# schematic_v1.net
KiCad netlist of a schematic drawn in EasyEDA
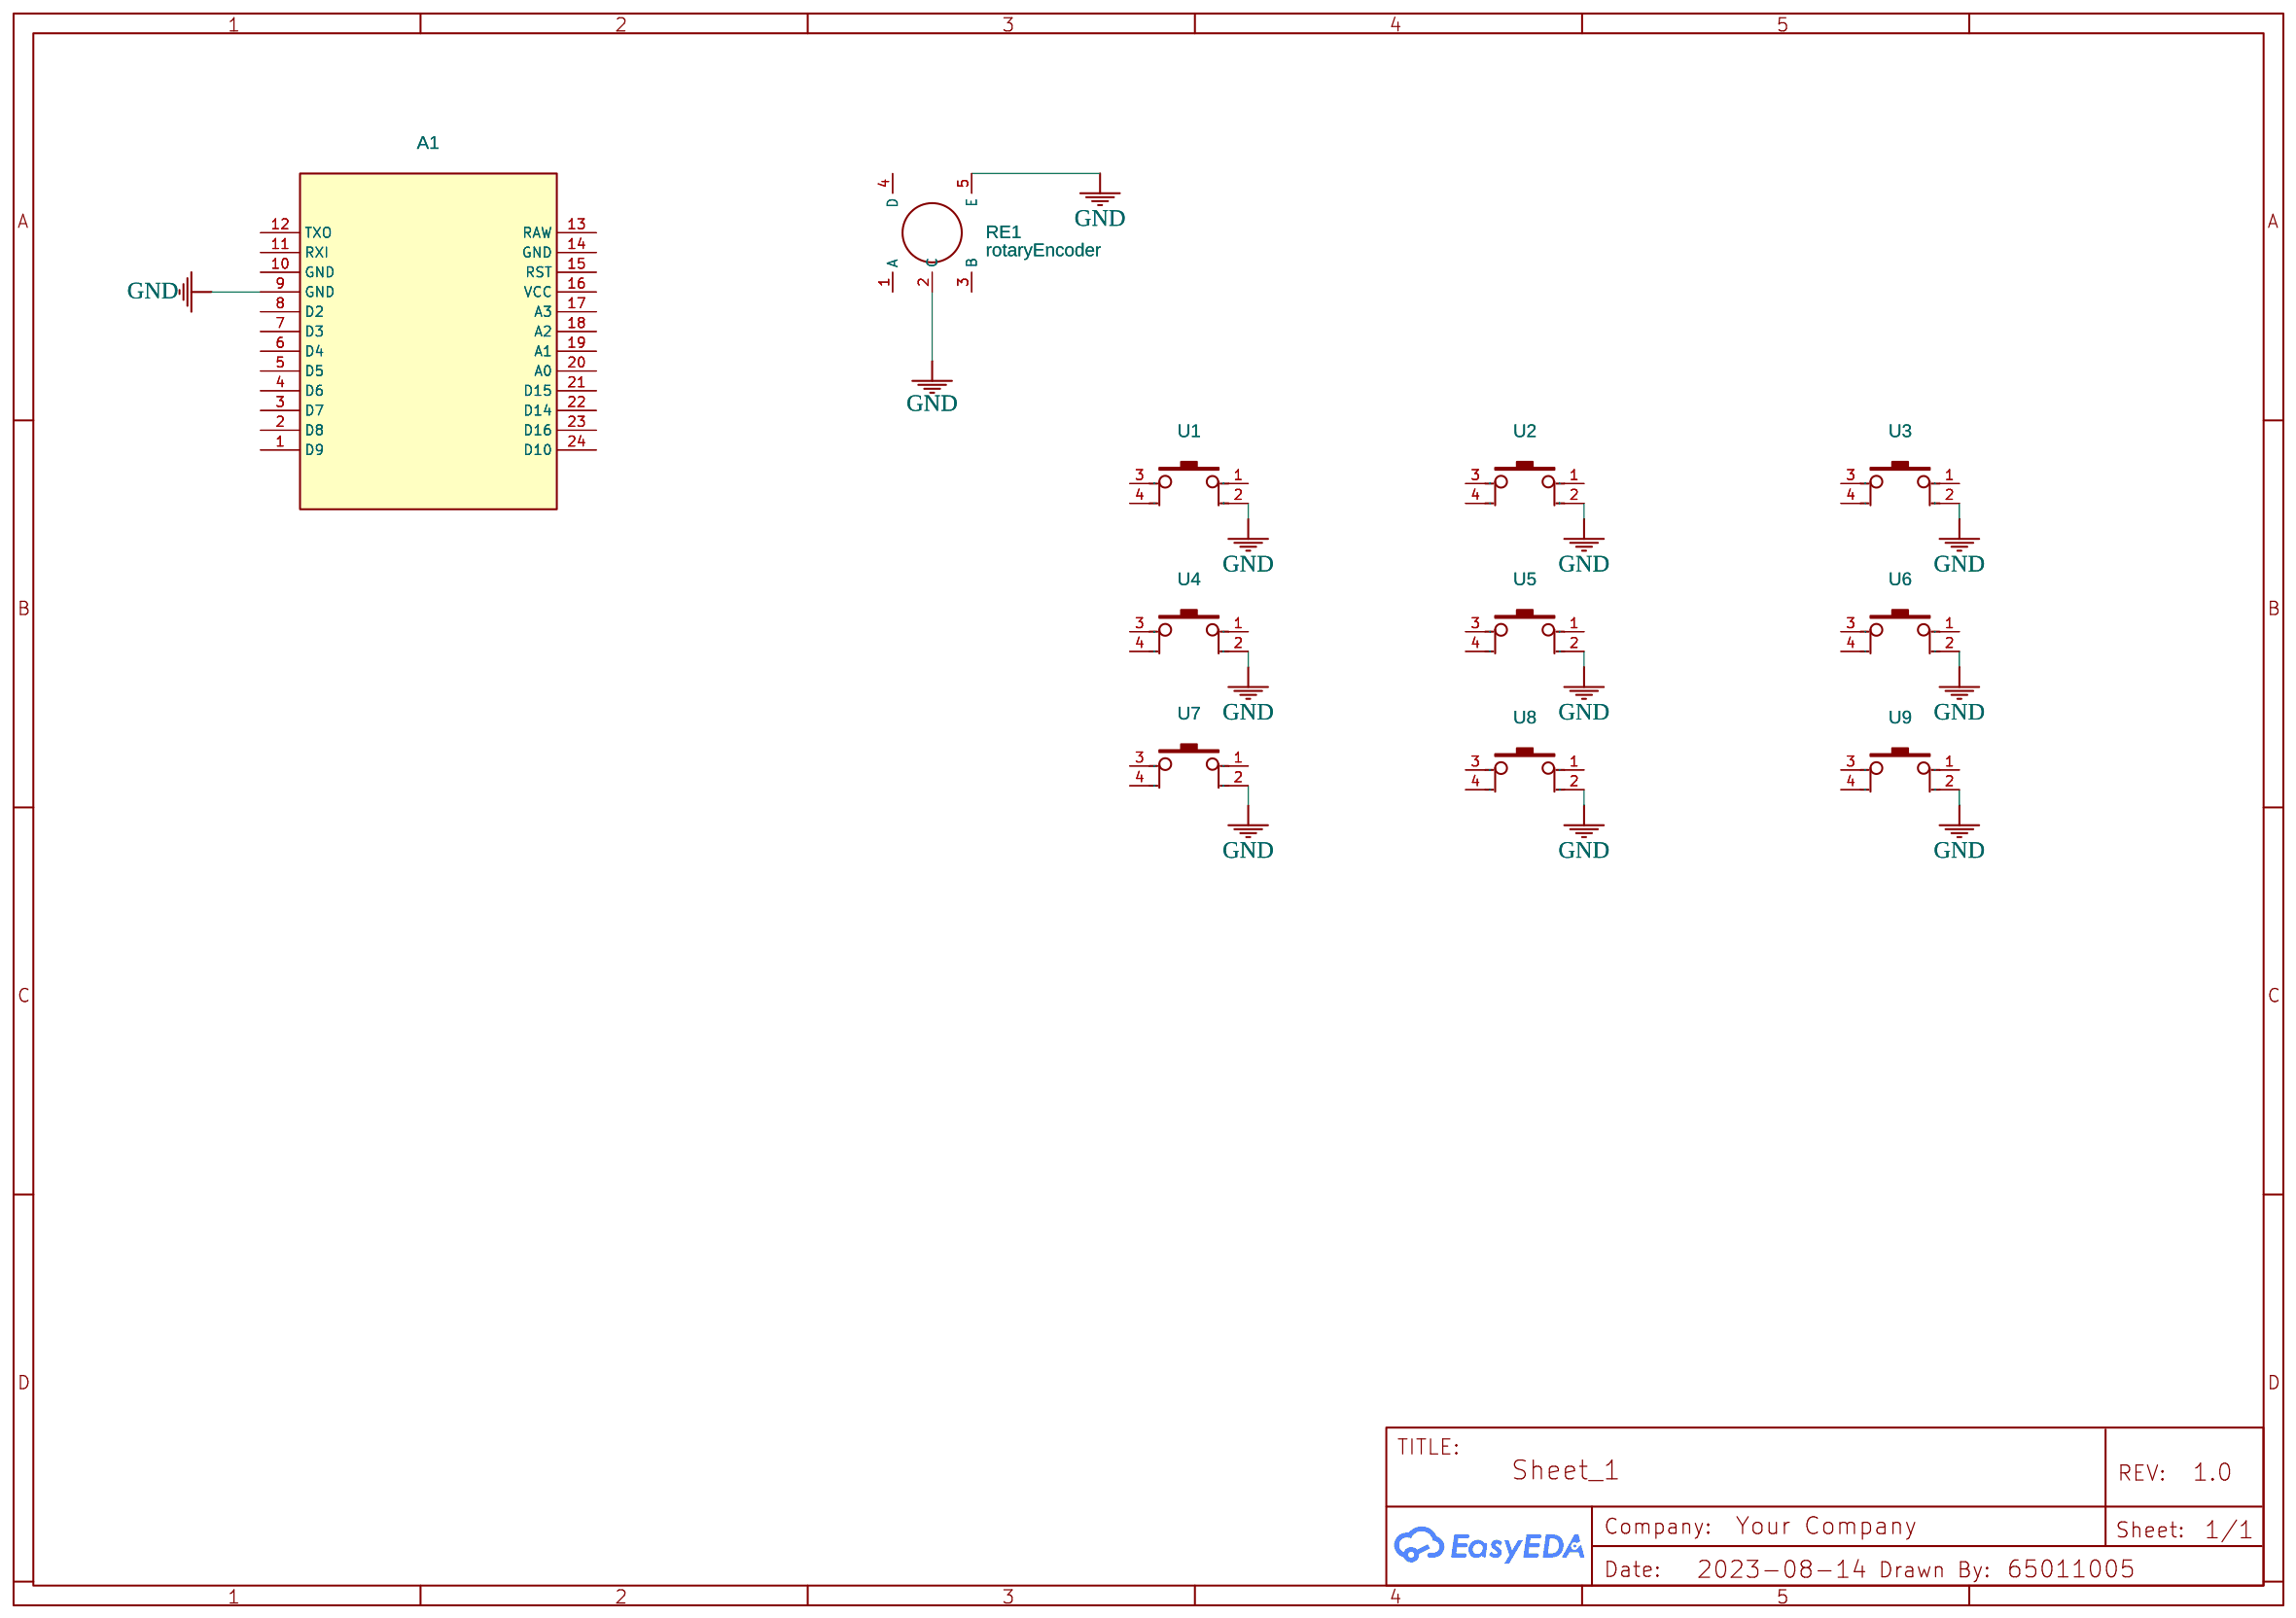
[diagram p0: schematic sheet]

(export (version "E")
  (design (tool "Eeschema 10.0.6"))
  (components
    (comp (ref "A1") (value "NO") (libsource (lib "") (part "Pro Micro - 5V")))
    (comp (ref "RE1") (value "rotaryEncoder") (libsource (lib "") (part "rotaryEncoder")))
    (comp (ref "U1") (value "NO") (libsource (lib "") (part "10mm pushbutton switch")))
    (comp (ref "U2") (value "NO") (libsource (lib "") (part "10mm pushbutton switch")))
    (comp (ref "U3") (value "NO") (libsource (lib "") (part "10mm pushbutton switch")))
    (comp (ref "U4") (value "NO") (libsource (lib "") (part "10mm pushbutton switch")))
    (comp (ref "U5") (value "NO") (libsource (lib "") (part "10mm pushbutton switch")))
    (comp (ref "U6") (value "NO") (libsource (lib "") (part "10mm pushbutton switch")))
    (comp (ref "U7") (value "NO") (libsource (lib "") (part "10mm pushbutton switch")))
    (comp (ref "U8") (value "NO") (libsource (lib "") (part "10mm pushbutton switch")))
    (comp (ref "U9") (value "NO") (libsource (lib "") (part "10mm pushbutton switch")))
  )
  (nets
    (net (code "1") (name "GND") (class "Default")
      (node (ref "A1") (pin "9") (pinfunction "GND_9") (pintype "unspecified"))
      (node (ref "RE1") (pin "2") (pinfunction "C_2") (pintype "unspecified"))
      (node (ref "RE1") (pin "5") (pinfunction "E_5") (pintype "unspecified"))
      (node (ref "U1") (pin "2") (pinfunction "2_2") (pintype "input"))
      (node (ref "U2") (pin "2") (pinfunction "2_2") (pintype "input"))
      (node (ref "U3") (pin "2") (pinfunction "2_2") (pintype "input"))
      (node (ref "U4") (pin "2") (pinfunction "2_2") (pintype "input"))
      (node (ref "U5") (pin "2") (pinfunction "2_2") (pintype "input"))
      (node (ref "U6") (pin "2") (pinfunction "2_2") (pintype "input"))
      (node (ref "U7") (pin "2") (pinfunction "2_2") (pintype "input"))
      (node (ref "U8") (pin "2") (pinfunction "2_2") (pintype "input"))
      (node (ref "U9") (pin "2") (pinfunction "2_2") (pintype "input"))
    )
    (net (code "2") (name "unconnected-(A1-A0-Pad20)") (class "Default")
      (node (ref "A1") (pin "20") (pinfunction "A0_20") (pintype "unspecified"))
    )
    (net (code "3") (name "unconnected-(A1-A1-Pad19)") (class "Default")
      (node (ref "A1") (pin "19") (pinfunction "A1_19") (pintype "unspecified"))
    )
    (net (code "4") (name "unconnected-(A1-A2-Pad18)") (class "Default")
      (node (ref "A1") (pin "18") (pinfunction "A2_18") (pintype "unspecified"))
    )
    (net (code "5") (name "unconnected-(A1-A3-Pad17)") (class "Default")
      (node (ref "A1") (pin "17") (pinfunction "A3_17") (pintype "unspecified"))
    )
    (net (code "6") (name "unconnected-(A1-D2-Pad8)") (class "Default")
      (node (ref "A1") (pin "8") (pinfunction "D2_8") (pintype "unspecified"))
    )
    (net (code "7") (name "unconnected-(A1-D3-Pad7)") (class "Default")
      (node (ref "A1") (pin "7") (pinfunction "D3_7") (pintype "unspecified"))
    )
    (net (code "8") (name "unconnected-(A1-D4-Pad6)") (class "Default")
      (node (ref "A1") (pin "6") (pinfunction "D4_6") (pintype "unspecified"))
    )
    (net (code "9") (name "unconnected-(A1-D5-Pad5)") (class "Default")
      (node (ref "A1") (pin "5") (pinfunction "D5_5") (pintype "unspecified"))
    )
    (net (code "10") (name "unconnected-(A1-D6-Pad4)") (class "Default")
      (node (ref "A1") (pin "4") (pinfunction "D6_4") (pintype "unspecified"))
    )
    (net (code "11") (name "unconnected-(A1-D7-Pad3)") (class "Default")
      (node (ref "A1") (pin "3") (pinfunction "D7_3") (pintype "unspecified"))
    )
    (net (code "12") (name "unconnected-(A1-D8-Pad2)") (class "Default")
      (node (ref "A1") (pin "2") (pinfunction "D8_2") (pintype "unspecified"))
    )
    (net (code "13") (name "unconnected-(A1-D9-Pad1)") (class "Default")
      (node (ref "A1") (pin "1") (pinfunction "D9_1") (pintype "unspecified"))
    )
    (net (code "14") (name "unconnected-(A1-D10-Pad24)") (class "Default")
      (node (ref "A1") (pin "24") (pinfunction "D10_24") (pintype "unspecified"))
    )
    (net (code "15") (name "unconnected-(A1-D14-Pad22)") (class "Default")
      (node (ref "A1") (pin "22") (pinfunction "D14_22") (pintype "unspecified"))
    )
    (net (code "16") (name "unconnected-(A1-D15-Pad21)") (class "Default")
      (node (ref "A1") (pin "21") (pinfunction "D15_21") (pintype "unspecified"))
    )
    (net (code "17") (name "unconnected-(A1-D16-Pad23)") (class "Default")
      (node (ref "A1") (pin "23") (pinfunction "D16_23") (pintype "unspecified"))
    )
    (net (code "18") (name "unconnected-(A1-GND-Pad10)") (class "Default")
      (node (ref "A1") (pin "10") (pinfunction "GND_10") (pintype "unspecified"))
    )
    (net (code "19") (name "unconnected-(A1-GND-Pad14)") (class "Default")
      (node (ref "A1") (pin "14") (pinfunction "GND_14") (pintype "unspecified"))
    )
    (net (code "20") (name "unconnected-(A1-RAW-Pad13)") (class "Default")
      (node (ref "A1") (pin "13") (pinfunction "RAW_13") (pintype "unspecified"))
    )
    (net (code "21") (name "unconnected-(A1-RST-Pad15)") (class "Default")
      (node (ref "A1") (pin "15") (pinfunction "RST_15") (pintype "unspecified"))
    )
    (net (code "22") (name "unconnected-(A1-RXI-Pad11)") (class "Default")
      (node (ref "A1") (pin "11") (pinfunction "RXI_11") (pintype "unspecified"))
    )
    (net (code "23") (name "unconnected-(A1-TXO-Pad12)") (class "Default")
      (node (ref "A1") (pin "12") (pinfunction "TXO_12") (pintype "unspecified"))
    )
    (net (code "24") (name "unconnected-(A1-VCC-Pad16)") (class "Default")
      (node (ref "A1") (pin "16") (pinfunction "VCC_16") (pintype "unspecified"))
    )
    (net (code "25") (name "unconnected-(RE1-A-Pad1)") (class "Default")
      (node (ref "RE1") (pin "1") (pinfunction "A_1") (pintype "unspecified"))
    )
    (net (code "26") (name "unconnected-(RE1-B-Pad3)") (class "Default")
      (node (ref "RE1") (pin "3") (pinfunction "B_3") (pintype "unspecified"))
    )
    (net (code "27") (name "unconnected-(RE1-D-Pad4)") (class "Default")
      (node (ref "RE1") (pin "4") (pinfunction "D_4") (pintype "unspecified"))
    )
    (net (code "28") (name "unconnected-(U1-Pad1)") (class "Default")
      (node (ref "U1") (pin "1") (pinfunction "1_1") (pintype "input"))
    )
    (net (code "29") (name "unconnected-(U1-Pad3)") (class "Default")
      (node (ref "U1") (pin "3") (pinfunction "3_3") (pintype "input"))
    )
    (net (code "30") (name "unconnected-(U1-Pad4)") (class "Default")
      (node (ref "U1") (pin "4") (pinfunction "4_4") (pintype "input"))
    )
    (net (code "31") (name "unconnected-(U2-Pad1)") (class "Default")
      (node (ref "U2") (pin "1") (pinfunction "1_1") (pintype "input"))
    )
    (net (code "32") (name "unconnected-(U2-Pad3)") (class "Default")
      (node (ref "U2") (pin "3") (pinfunction "3_3") (pintype "input"))
    )
    (net (code "33") (name "unconnected-(U2-Pad4)") (class "Default")
      (node (ref "U2") (pin "4") (pinfunction "4_4") (pintype "input"))
    )
    (net (code "34") (name "unconnected-(U3-Pad1)") (class "Default")
      (node (ref "U3") (pin "1") (pinfunction "1_1") (pintype "input"))
    )
    (net (code "35") (name "unconnected-(U3-Pad3)") (class "Default")
      (node (ref "U3") (pin "3") (pinfunction "3_3") (pintype "input"))
    )
    (net (code "36") (name "unconnected-(U3-Pad4)") (class "Default")
      (node (ref "U3") (pin "4") (pinfunction "4_4") (pintype "input"))
    )
    (net (code "37") (name "unconnected-(U4-Pad1)") (class "Default")
      (node (ref "U4") (pin "1") (pinfunction "1_1") (pintype "input"))
    )
    (net (code "38") (name "unconnected-(U4-Pad3)") (class "Default")
      (node (ref "U4") (pin "3") (pinfunction "3_3") (pintype "input"))
    )
    (net (code "39") (name "unconnected-(U4-Pad4)") (class "Default")
      (node (ref "U4") (pin "4") (pinfunction "4_4") (pintype "input"))
    )
    (net (code "40") (name "unconnected-(U5-Pad1)") (class "Default")
      (node (ref "U5") (pin "1") (pinfunction "1_1") (pintype "input"))
    )
    (net (code "41") (name "unconnected-(U5-Pad3)") (class "Default")
      (node (ref "U5") (pin "3") (pinfunction "3_3") (pintype "input"))
    )
    (net (code "42") (name "unconnected-(U5-Pad4)") (class "Default")
      (node (ref "U5") (pin "4") (pinfunction "4_4") (pintype "input"))
    )
    (net (code "43") (name "unconnected-(U6-Pad1)") (class "Default")
      (node (ref "U6") (pin "1") (pinfunction "1_1") (pintype "input"))
    )
    (net (code "44") (name "unconnected-(U6-Pad3)") (class "Default")
      (node (ref "U6") (pin "3") (pinfunction "3_3") (pintype "input"))
    )
    (net (code "45") (name "unconnected-(U6-Pad4)") (class "Default")
      (node (ref "U6") (pin "4") (pinfunction "4_4") (pintype "input"))
    )
    (net (code "46") (name "unconnected-(U7-Pad1)") (class "Default")
      (node (ref "U7") (pin "1") (pinfunction "1_1") (pintype "input"))
    )
    (net (code "47") (name "unconnected-(U7-Pad3)") (class "Default")
      (node (ref "U7") (pin "3") (pinfunction "3_3") (pintype "input"))
    )
    (net (code "48") (name "unconnected-(U7-Pad4)") (class "Default")
      (node (ref "U7") (pin "4") (pinfunction "4_4") (pintype "input"))
    )
    (net (code "49") (name "unconnected-(U8-Pad1)") (class "Default")
      (node (ref "U8") (pin "1") (pinfunction "1_1") (pintype "input"))
    )
    (net (code "50") (name "unconnected-(U8-Pad3)") (class "Default")
      (node (ref "U8") (pin "3") (pinfunction "3_3") (pintype "input"))
    )
    (net (code "51") (name "unconnected-(U8-Pad4)") (class "Default")
      (node (ref "U8") (pin "4") (pinfunction "4_4") (pintype "input"))
    )
    (net (code "52") (name "unconnected-(U9-Pad1)") (class "Default")
      (node (ref "U9") (pin "1") (pinfunction "1_1") (pintype "input"))
    )
    (net (code "53") (name "unconnected-(U9-Pad3)") (class "Default")
      (node (ref "U9") (pin "3") (pinfunction "3_3") (pintype "input"))
    )
    (net (code "54") (name "unconnected-(U9-Pad4)") (class "Default")
      (node (ref "U9") (pin "4") (pinfunction "4_4") (pintype "input"))
    )
  )
)
